# ESP32.net
KiCad netlist of a schematic drawn in EasyEDA
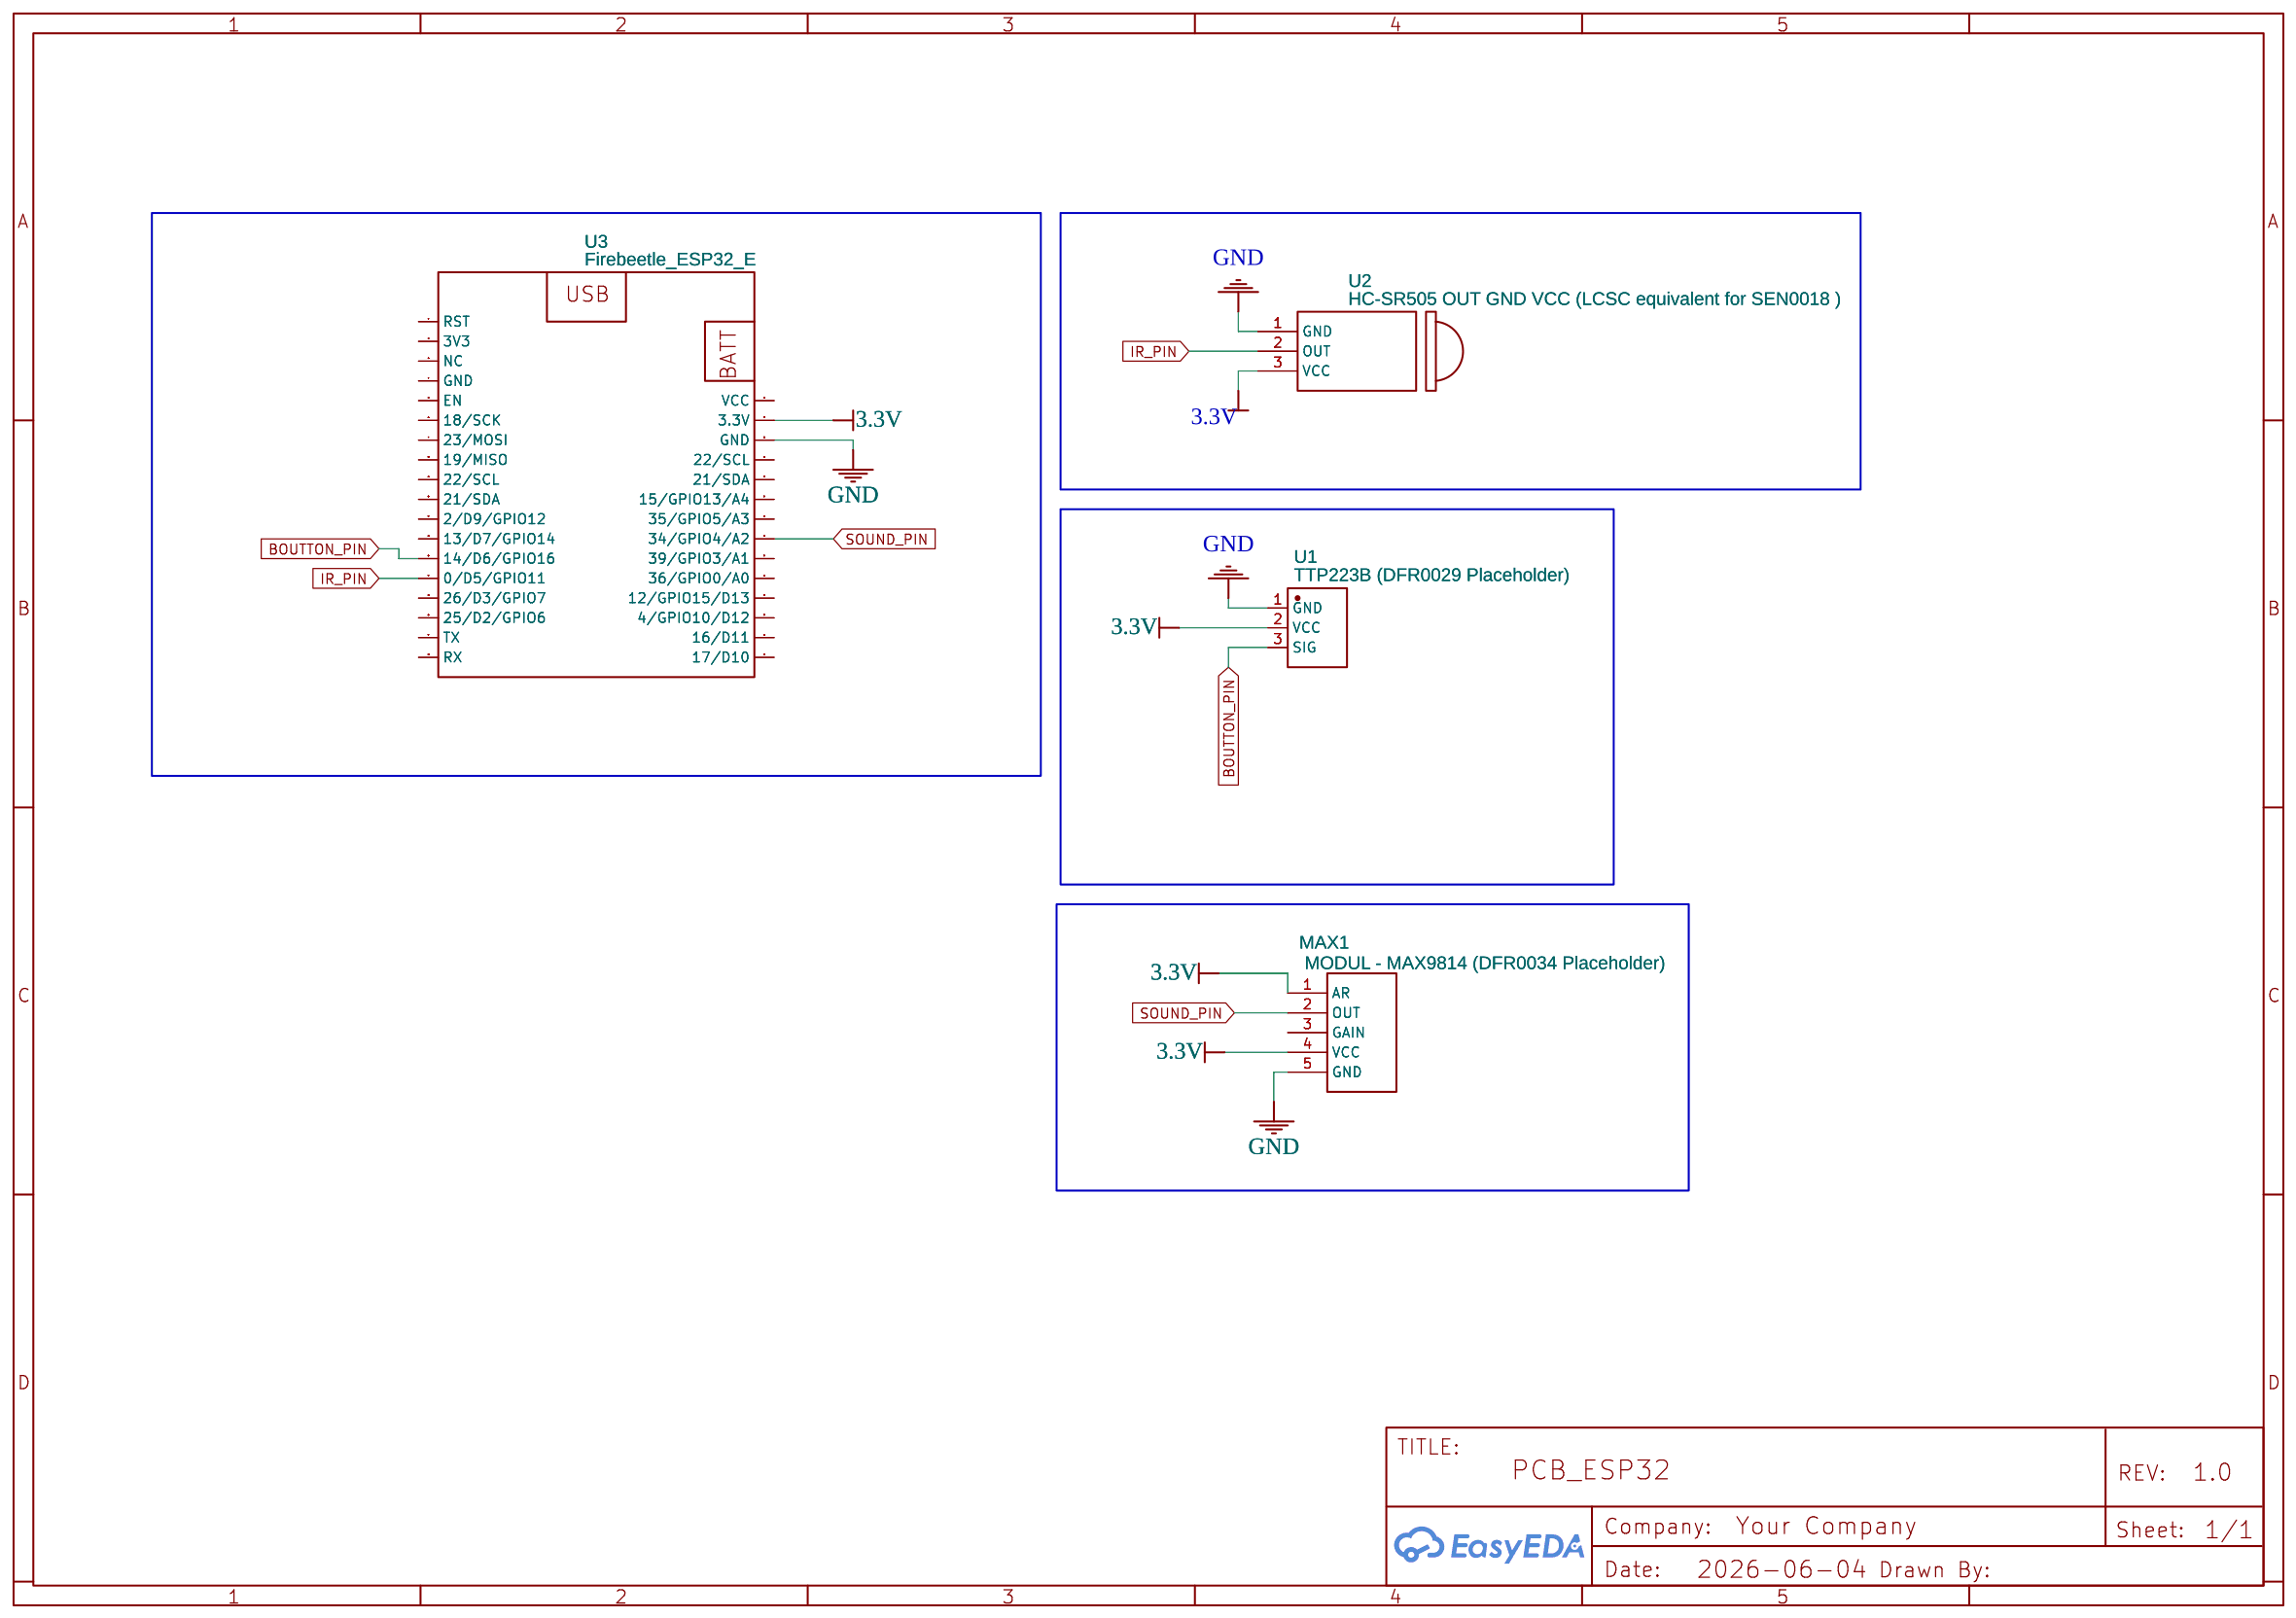
[diagram p0: schematic sheet]

(export (version "E")
  (design (tool "Eeschema 10.0.6"))
  (components
    (comp (ref "MAX1")
      (value "MODUL - MAX9814 (DFR0034 Placeholder)")
      (libsource (lib "") (part "MODUL - MAX9814"))
    )
    (comp (ref "U1") (value "TTP223B (DFR0029 Placeholder)") (libsource (lib "") (part "TTP223B")))
    (comp (ref "U2")
      (value "HC-SR505 OUT GND VCC (LCSC equivalent for SEN0018 )")
      (libsource (lib "") (part "HC-SR505 OUT GND VCC"))
    )
    (comp (ref "U3")
      (value "Firebeetle_ESP32_E")
      (fields (field (name "Manufacturer Part") "DFR0654") (field (name "Manufacturer") "DFRobot"))
      (libsource (lib "") (part "Firebeetle_ESP32_E"))
    )
  )
  (nets
    (net (code "1") (name "3.3V") (class "Default")
      (node (ref "MAX1") (pin "1") (pinfunction "AR_1") (pintype "unspecified"))
      (node (ref "MAX1") (pin "4") (pinfunction "VCC_4") (pintype "unspecified"))
      (node (ref "U1") (pin "2") (pinfunction "VCC_2") (pintype "unspecified"))
      (node (ref "U2") (pin "3") (pinfunction "VCC_3") (pintype "unspecified"))
      (node (ref "U3") (pin "31") (pinfunction "3.3V_31") (pintype "unspecified"))
    )
    (net (code "2") (name "BOUTTON_PIN") (class "Default")
      (node (ref "U1") (pin "3") (pinfunction "SIG_3") (pintype "unspecified"))
      (node (ref "U3") (pin "13") (pinfunction "14/D6/GPIO16_13") (pintype "unspecified"))
    )
    (net (code "3") (name "GND") (class "Default")
      (node (ref "MAX1") (pin "5") (pinfunction "GND_5") (pintype "unspecified"))
      (node (ref "U1") (pin "1") (pinfunction "GND_1") (pintype "unspecified"))
      (node (ref "U2") (pin "1") (pinfunction "GND_1") (pintype "unspecified"))
      (node (ref "U3") (pin "30") (pinfunction "GND_30") (pintype "unspecified"))
    )
    (net (code "4") (name "IR_PIN") (class "Default")
      (node (ref "U2") (pin "2") (pinfunction "OUT_2") (pintype "unspecified"))
      (node (ref "U3") (pin "14") (pinfunction "0/D5/GPIO11_14") (pintype "unspecified"))
    )
    (net (code "5") (name "SOUND_PIN") (class "Default")
      (node (ref "MAX1") (pin "2") (pinfunction "OUT_2") (pintype "unspecified"))
      (node (ref "U3") (pin "25") (pinfunction "34/GPIO4/A2_25") (pintype "unspecified"))
    )
    (net (code "6") (name "unconnected-(MAX1-GAIN-Pad3)") (class "Default")
      (node (ref "MAX1") (pin "3") (pinfunction "GAIN_3") (pintype "unspecified"))
    )
    (net (code "7") (name "unconnected-(U3-2{slash}D9{slash}GPIO12-Pad11)") (class "Default")
      (node (ref "U3") (pin "11") (pinfunction "2/D9/GPIO12_11") (pintype "unspecified"))
    )
    (net (code "8") (name "unconnected-(U3-3V3-Pad2)") (class "Default")
      (node (ref "U3") (pin "2") (pinfunction "3V3_2") (pintype "unspecified"))
    )
    (net (code "9") (name "unconnected-(U3-4{slash}GPIO10{slash}D12-Pad21)") (class "Default")
      (node (ref "U3") (pin "21") (pinfunction "4/GPIO10/D12_21") (pintype "unspecified"))
    )
    (net (code "10") (name "unconnected-(U3-12{slash}GPIO15{slash}D13-Pad22)") (class "Default")
      (node (ref "U3") (pin "22") (pinfunction "12/GPIO15/D13_22") (pintype "unspecified"))
    )
    (net (code "11") (name "unconnected-(U3-13{slash}D7{slash}GPIO14-Pad12)") (class "Default")
      (node (ref "U3") (pin "12") (pinfunction "13/D7/GPIO14_12") (pintype "unspecified"))
    )
    (net (code "12") (name "unconnected-(U3-15{slash}GPIO13{slash}A4-Pad27)") (class "Default")
      (node (ref "U3") (pin "27") (pinfunction "15/GPIO13/A4_27") (pintype "unspecified"))
    )
    (net (code "13") (name "unconnected-(U3-16{slash}D11-Pad20)") (class "Default")
      (node (ref "U3") (pin "20") (pinfunction "16/D11_20") (pintype "unspecified"))
    )
    (net (code "14") (name "unconnected-(U3-17{slash}D10-Pad19)") (class "Default")
      (node (ref "U3") (pin "19") (pinfunction "17/D10_19") (pintype "unspecified"))
    )
    (net (code "15") (name "unconnected-(U3-18{slash}SCK-Pad6)") (class "Default")
      (node (ref "U3") (pin "6") (pinfunction "18/SCK_6") (pintype "unspecified"))
    )
    (net (code "16") (name "unconnected-(U3-19{slash}MISO-Pad8)") (class "Default")
      (node (ref "U3") (pin "8") (pinfunction "19/MISO_8") (pintype "unspecified"))
    )
    (net (code "17") (name "unconnected-(U3-21{slash}SDA-Pad10)") (class "Default")
      (node (ref "U3") (pin "10") (pinfunction "21/SDA_10") (pintype "unspecified"))
    )
    (net (code "18") (name "unconnected-(U3-21{slash}SDA-Pad28)") (class "Default")
      (node (ref "U3") (pin "28") (pinfunction "21/SDA_28") (pintype "unspecified"))
    )
    (net (code "19") (name "unconnected-(U3-22{slash}SCL-Pad9)") (class "Default")
      (node (ref "U3") (pin "9") (pinfunction "22/SCL_9") (pintype "unspecified"))
    )
    (net (code "20") (name "unconnected-(U3-22{slash}SCL-Pad29)") (class "Default")
      (node (ref "U3") (pin "29") (pinfunction "22/SCL_29") (pintype "unspecified"))
    )
    (net (code "21") (name "unconnected-(U3-23{slash}MOSI-Pad7)") (class "Default")
      (node (ref "U3") (pin "7") (pinfunction "23/MOSI_7") (pintype "unspecified"))
    )
    (net (code "22") (name "unconnected-(U3-25{slash}D2{slash}GPIO6-Pad16)") (class "Default")
      (node (ref "U3") (pin "16") (pinfunction "25/D2/GPIO6_16") (pintype "unspecified"))
    )
    (net (code "23") (name "unconnected-(U3-26{slash}D3{slash}GPIO7-Pad15)") (class "Default")
      (node (ref "U3") (pin "15") (pinfunction "26/D3/GPIO7_15") (pintype "unspecified"))
    )
    (net (code "24") (name "unconnected-(U3-35{slash}GPIO5{slash}A3-Pad26)") (class "Default")
      (node (ref "U3") (pin "26") (pinfunction "35/GPIO5/A3_26") (pintype "unspecified"))
    )
    (net (code "25") (name "unconnected-(U3-36{slash}GPIO0{slash}A0-Pad23)") (class "Default")
      (node (ref "U3") (pin "23") (pinfunction "36/GPIO0/A0_23") (pintype "unspecified"))
    )
    (net (code "26") (name "unconnected-(U3-39{slash}GPIO3{slash}A1-Pad24)") (class "Default")
      (node (ref "U3") (pin "24") (pinfunction "39/GPIO3/A1_24") (pintype "unspecified"))
    )
    (net (code "27") (name "unconnected-(U3-EN-Pad5)") (class "Default")
      (node (ref "U3") (pin "5") (pinfunction "EN_5") (pintype "unspecified"))
    )
    (net (code "28") (name "unconnected-(U3-GND-Pad4)") (class "Default")
      (node (ref "U3") (pin "4") (pinfunction "GND_4") (pintype "unspecified"))
    )
    (net (code "29") (name "unconnected-(U3-NC-Pad3)") (class "Default")
      (node (ref "U3") (pin "3") (pinfunction "NC_3") (pintype "unspecified"))
    )
    (net (code "30") (name "unconnected-(U3-RST-Pad1)") (class "Default")
      (node (ref "U3") (pin "1") (pinfunction "RST_1") (pintype "unspecified"))
    )
    (net (code "31") (name "unconnected-(U3-RX-Pad18)") (class "Default")
      (node (ref "U3") (pin "18") (pinfunction "RX_18") (pintype "unspecified"))
    )
    (net (code "32") (name "unconnected-(U3-TX-Pad17)") (class "Default")
      (node (ref "U3") (pin "17") (pinfunction "TX_17") (pintype "unspecified"))
    )
    (net (code "33") (name "unconnected-(U3-VCC-Pad32)") (class "Default")
      (node (ref "U3") (pin "32") (pinfunction "VCC_32") (pintype "unspecified"))
    )
  )
)
